# FE.net
KiCad netlist of a schematic drawn in Altium Designer
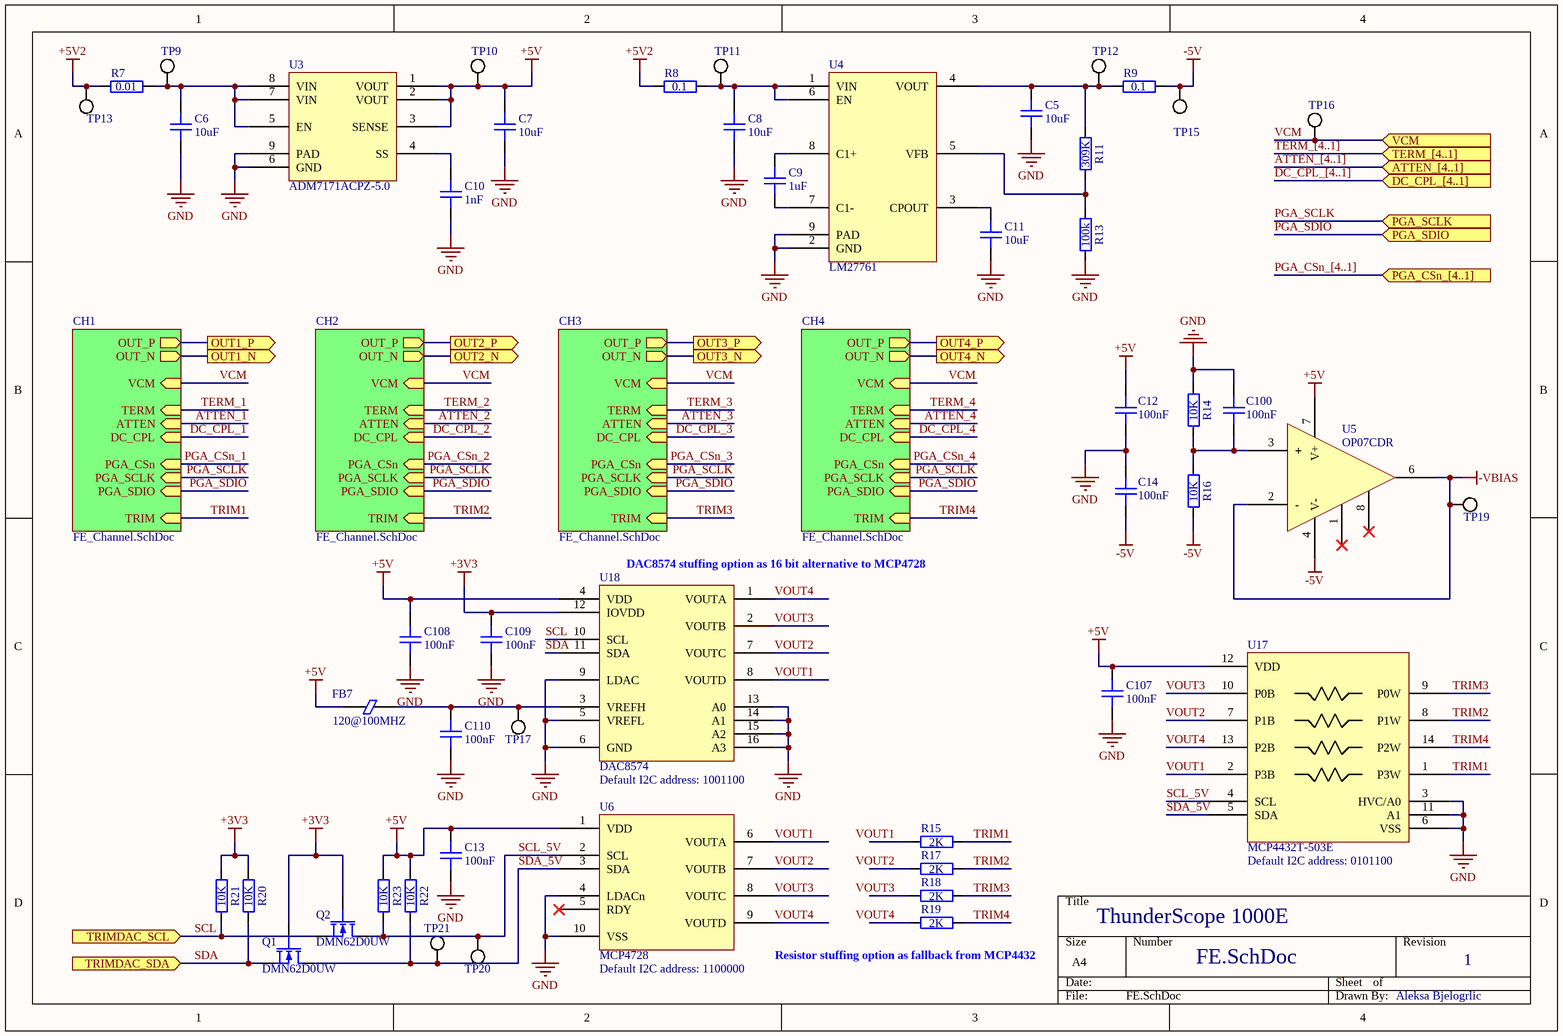
[diagram p0: FE.SchDoc]

(export (version "E")
  (design (tool "Eeschema 10.0.6"))
  (components
    (comp (ref "C5")
      (value "10uF")
      (footprint "GEN_C_0603")
      (libsource (lib "DSO") (part "CAP 10uF 10V X5R 0603"))
    )
    (comp (ref "C6")
      (value "10uF")
      (footprint "GEN_C_0603")
      (libsource (lib "DSO") (part "CAP 10uF 10V X5R 0603"))
    )
    (comp (ref "C7")
      (value "10uF")
      (footprint "GEN_C_0603")
      (libsource (lib "DSO") (part "CAP 10uF 10V X5R 0603"))
    )
    (comp (ref "C8")
      (value "10uF")
      (footprint "GEN_C_0603")
      (libsource (lib "DSO") (part "CAP 10uF 10V X5R 0603"))
    )
    (comp (ref "C9")
      (value "1uF")
      (footprint "GEN_C_0402")
      (libsource (lib "DSO") (part "CAP 1uF 25V X5R 0402"))
    )
    (comp (ref "C10")
      (value "1nF")
      (footprint "GEN_C_0402")
      (libsource (lib "DSO") (part "CAP 1nF 50V C0G 0402"))
    )
    (comp (ref "C11")
      (value "10uF")
      (footprint "GEN_C_0603")
      (libsource (lib "DSO") (part "CAP 10uF 10V X5R 0603"))
    )
    (comp (ref "C12")
      (value "100nF")
      (footprint "GEN_C_0402")
      (libsource (lib "DSO") (part "CAP 100nF 16V X7R 0402"))
    )
    (comp (ref "C13")
      (value "100nF")
      (footprint "GEN_C_0402")
      (libsource (lib "DSO") (part "CAP 100nF 16V X7R 0402"))
    )
    (comp (ref "C14")
      (value "100nF")
      (footprint "GEN_C_0402")
      (libsource (lib "DSO") (part "CAP 100nF 16V X7R 0402"))
    )
    (comp (ref "C100")
      (value "100nF")
      (footprint "GEN_C_0402")
      (libsource (lib "DSO") (part "CAP 100nF 16V X7R 0402"))
    )
    (comp (ref "C107")
      (value "100nF")
      (footprint "GEN_C_0402")
      (libsource (lib "DSO") (part "CAP 100nF 16V X7R 0402"))
    )
    (comp (ref "C108")
      (value "100nF")
      (footprint "GEN_C_0402")
      (libsource (lib "DSO") (part "CAP 100nF 16V X7R 0402"))
    )
    (comp (ref "C109")
      (value "100nF")
      (footprint "GEN_C_0402")
      (libsource (lib "DSO") (part "CAP 100nF 16V X7R 0402"))
    )
    (comp (ref "C110")
      (value "100nF")
      (footprint "GEN_C_0402")
      (libsource (lib "DSO") (part "CAP 100nF 16V X7R 0402"))
    )
    (comp (ref "FB7")
      (value "120@100MHZ")
      (footprint "GEN_R_0402")
      (libsource (lib "DSO") (part "FERRITE BEAD 120 OHM 0402"))
    )
    (comp (ref "Q1")
      (value "DMN62D0UW")
      (footprint "GEN_SOT_323")
      (libsource (lib "DSO") (part "NMOS DMN62D0UW"))
    )
    (comp (ref "Q2")
      (value "DMN62D0UW")
      (footprint "GEN_SOT_323")
      (libsource (lib "DSO") (part "NMOS DMN62D0UW"))
    )
    (comp (ref "R7")
      (value "0.01")
      (footprint "GEN_R_0603")
      (fields (field (name "TOLERANCE") "1%"))
      (libsource (lib "DSO") (part "RES 0.01 OHM 1% 1/4W 0603"))
    )
    (comp (ref "R8")
      (value "0.1")
      (footprint "GEN_R_0402")
      (fields (field (name "TOLERANCE") "1%"))
      (libsource (lib "DSO") (part "RES 0.1 OHM 1% 1/6W 0402"))
    )
    (comp (ref "R9")
      (value "0.1")
      (footprint "GEN_R_0402")
      (fields (field (name "TOLERANCE") "1%"))
      (libsource (lib "DSO") (part "RES 0.1 OHM 1% 1/6W 0402"))
    )
    (comp (ref "R11")
      (value "309K")
      (footprint "GEN_R_0402")
      (fields (field (name "TOLERANCE") "1%"))
      (libsource (lib "DSO") (part "RES 309K OHM 1% 1/16W 0402"))
    )
    (comp (ref "R13")
      (value "100k")
      (footprint "GEN_R_0402")
      (fields (field (name "TOLERANCE") "1%"))
      (libsource (lib "DSO") (part "RES 100K OHM 1% 1/10W 0402"))
    )
    (comp (ref "R14")
      (value "10K")
      (footprint "GEN_R_0402")
      (fields (field (name "TOLERANCE") "1%"))
      (libsource (lib "DSO") (part "RES 10K OHM 1% 1/10W 0402"))
    )
    (comp (ref "R15")
      (value "2K")
      (footprint "GEN_R_0402")
      (fields (field (name "TOLERANCE") "1%"))
      (libsource (lib "DSO") (part "RES 2K OHM 1% 1/16W 0402"))
    )
    (comp (ref "R16")
      (value "10K")
      (footprint "GEN_R_0402")
      (fields (field (name "TOLERANCE") "1%"))
      (libsource (lib "DSO") (part "RES 10K OHM 1% 1/10W 0402"))
    )
    (comp (ref "R17")
      (value "2K")
      (footprint "GEN_R_0402")
      (fields (field (name "TOLERANCE") "1%"))
      (libsource (lib "DSO") (part "RES 2K OHM 1% 1/16W 0402"))
    )
    (comp (ref "R18")
      (value "2K")
      (footprint "GEN_R_0402")
      (fields (field (name "TOLERANCE") "1%"))
      (libsource (lib "DSO") (part "RES 2K OHM 1% 1/16W 0402"))
    )
    (comp (ref "R19")
      (value "2K")
      (footprint "GEN_R_0402")
      (fields (field (name "TOLERANCE") "1%"))
      (libsource (lib "DSO") (part "RES 2K OHM 1% 1/16W 0402"))
    )
    (comp (ref "R20")
      (value "10K")
      (footprint "GEN_R_0402")
      (fields (field (name "TOLERANCE") "1%"))
      (libsource (lib "DSO") (part "RES 10K OHM 1% 1/10W 0402"))
    )
    (comp (ref "R21")
      (value "10K")
      (footprint "GEN_R_0402")
      (fields (field (name "TOLERANCE") "1%"))
      (libsource (lib "DSO") (part "RES 10K OHM 1% 1/10W 0402"))
    )
    (comp (ref "R22")
      (value "10K")
      (footprint "GEN_R_0402")
      (fields (field (name "TOLERANCE") "1%"))
      (libsource (lib "DSO") (part "RES 10K OHM 1% 1/10W 0402"))
    )
    (comp (ref "R23")
      (value "10K")
      (footprint "GEN_R_0402")
      (fields (field (name "TOLERANCE") "1%"))
      (libsource (lib "DSO") (part "RES 10K OHM 1% 1/10W 0402"))
    )
    (comp (ref "TP9") (value "PCB") (footprint "GEN_TP_PCB") (libsource (lib "DSO") (part "TP PCB 1mm")))
    (comp (ref "TP10") (value "PCB") (footprint "GEN_TP_PCB") (libsource (lib "DSO") (part "TP PCB 1mm")))
    (comp (ref "TP11") (value "PCB") (footprint "GEN_TP_PCB") (libsource (lib "DSO") (part "TP PCB 1mm")))
    (comp (ref "TP12") (value "PCB") (footprint "GEN_TP_PCB") (libsource (lib "DSO") (part "TP PCB 1mm")))
    (comp (ref "TP13") (value "PCB") (footprint "GEN_TP_PCB") (libsource (lib "DSO") (part "TP PCB 1mm")))
    (comp (ref "TP15") (value "PCB") (footprint "GEN_TP_PCB") (libsource (lib "DSO") (part "TP PCB 1mm")))
    (comp (ref "TP16") (value "PCB") (footprint "GEN_TP_PCB") (libsource (lib "DSO") (part "TP PCB 1mm")))
    (comp (ref "TP17") (value "PCB") (footprint "GEN_TP_PCB") (libsource (lib "DSO") (part "TP PCB 1mm")))
    (comp (ref "TP19") (value "PCB") (footprint "GEN_TP_PCB") (libsource (lib "DSO") (part "TP PCB 1mm")))
    (comp (ref "TP20") (value "PCB") (footprint "GEN_TP_PCB") (libsource (lib "DSO") (part "TP PCB 1mm")))
    (comp (ref "TP21") (value "PCB") (footprint "GEN_TP_PCB") (libsource (lib "DSO") (part "TP PCB 1mm")))
    (comp (ref "U3")
      (value "ADM7171ACPZ-5.0")
      (footprint "AD_DFN8_CP-8-21")
      (libsource (lib "DSO") (part "IC LDO ADM7171ACPZ-5.0"))
    )
    (comp (ref "U4")
      (value "LM27761")
      (footprint "TI_WSON8_DSG0008A")
      (libsource (lib "DSO") (part "IC CPUMP LM27761"))
    )
    (comp (ref "U5")
      (value "OP07CDR")
      (footprint "TI_SOIC8_D0008A")
      (libsource (lib "DSO") (part "IC OPAMP OP07CDR"))
    )
    (comp (ref "U6")
      (value "MCP4728")
      (footprint "MC_MSOP10_UN")
      (libsource (lib "DSO") (part "IC DAC QUAD MCP4728"))
    )
    (comp (ref "U17")
      (value "MCP4432T-503E")
      (footprint "MC_TSSOP14")
      (libsource (lib "DSO") (part "IC DIGIPOT QUAD MCP4432T-503E"))
    )
    (comp (ref "U18")
      (value "DAC8574")
      (footprint "TI_TSSOP16_PW0016A")
      (libsource (lib "DSO") (part "IC DAC QUAD DAC8574"))
    )
  )
  (nets
    (net (code "1") (name "+3V3") (class "Default")
      (node (ref "C109") (pin "2") (pinfunction "2_2") (pintype "passive"))
      (node (ref "Q1") (pin "2") (pinfunction "G_2") (pintype "passive"))
      (node (ref "Q2") (pin "2") (pinfunction "G_2") (pintype "passive"))
      (node (ref "R20") (pin "2") (pinfunction "2_2") (pintype "passive"))
      (node (ref "R21") (pin "2") (pinfunction "2_2") (pintype "passive"))
      (node (ref "U18") (pin "12") (pinfunction "IOVDD_12") (pintype "power_in"))
    )
    (net (code "2") (name "+5V") (class "Default")
      (node (ref "C107") (pin "2") (pinfunction "2_2") (pintype "passive"))
      (node (ref "C108") (pin "2") (pinfunction "2_2") (pintype "passive"))
      (node (ref "C12") (pin "1") (pinfunction "1_1") (pintype "passive"))
      (node (ref "C13") (pin "2") (pinfunction "2_2") (pintype "passive"))
      (node (ref "C7") (pin "2") (pinfunction "2_2") (pintype "passive"))
      (node (ref "FB7") (pin "2") (pinfunction "2_2") (pintype "passive"))
      (node (ref "R22") (pin "2") (pinfunction "2_2") (pintype "passive"))
      (node (ref "R23") (pin "2") (pinfunction "2_2") (pintype "passive"))
      (node (ref "TP10") (pin "1") (pinfunction "1_1") (pintype "passive"))
      (node (ref "U17") (pin "12") (pinfunction "VDD_12") (pintype "power_in"))
      (node (ref "U18") (pin "4") (pinfunction "VDD_4") (pintype "power_in"))
      (node (ref "U3") (pin "1") (pinfunction "VOUT_1") (pintype "power_in"))
      (node (ref "U3") (pin "2") (pinfunction "VOUT_2") (pintype "power_in"))
      (node (ref "U3") (pin "3") (pinfunction "SENSE_3") (pintype "passive"))
      (node (ref "U5") (pin "7") (pinfunction "V+_7") (pintype "passive"))
      (node (ref "U6") (pin "1") (pinfunction "VDD_1") (pintype "power_in"))
    )
    (net (code "3") (name "+5V2") (class "Default")
      (node (ref "R7") (pin "1") (pinfunction "1_1") (pintype "passive"))
      (node (ref "R8") (pin "1") (pinfunction "1_1") (pintype "passive"))
      (node (ref "TP13") (pin "1") (pinfunction "1_1") (pintype "passive"))
    )
    (net (code "4") (name "-5V") (class "Default")
      (node (ref "C14") (pin "2") (pinfunction "2_2") (pintype "passive"))
      (node (ref "R16") (pin "1") (pinfunction "1_1") (pintype "passive"))
      (node (ref "R9") (pin "2") (pinfunction "2_2") (pintype "passive"))
      (node (ref "TP15") (pin "1") (pinfunction "1_1") (pintype "passive"))
      (node (ref "U5") (pin "4") (pinfunction "V-_4") (pintype "passive"))
    )
    (net (code "5") (name "-VBIAS") (class "Default")
      (node (ref "TP19") (pin "1") (pinfunction "1_1") (pintype "passive"))
      (node (ref "U5") (pin "2") (pinfunction "-_2") (pintype "passive"))
      (node (ref "U5") (pin "6") (pinfunction "OUT_6") (pintype "passive"))
    )
    (net (code "31") (name "/SCL") (class "Default")
      (node (ref "Q2") (pin "3") (pinfunction "S_3") (pintype "passive"))
      (node (ref "R21") (pin "1") (pinfunction "1_1") (pintype "passive"))
      (node (ref "U18") (pin "10") (pinfunction "SCL_10") (pintype "passive"))
    )
    (net (code "32") (name "/SCL_5V") (class "Default")
      (node (ref "Q2") (pin "1") (pinfunction "D_1") (pintype "passive"))
      (node (ref "R23") (pin "1") (pinfunction "1_1") (pintype "passive"))
      (node (ref "TP20") (pin "1") (pinfunction "1_1") (pintype "passive"))
      (node (ref "U17") (pin "4") (pinfunction "SCL_4") (pintype "passive"))
      (node (ref "U6") (pin "2") (pinfunction "SCL_2") (pintype "passive"))
    )
    (net (code "33") (name "/SDA") (class "Default")
      (node (ref "Q1") (pin "3") (pinfunction "S_3") (pintype "passive"))
      (node (ref "R20") (pin "1") (pinfunction "1_1") (pintype "passive"))
      (node (ref "U18") (pin "11") (pinfunction "SDA_11") (pintype "passive"))
    )
    (net (code "34") (name "/SDA_5V") (class "Default")
      (node (ref "Q1") (pin "1") (pinfunction "D_1") (pintype "passive"))
      (node (ref "R22") (pin "1") (pinfunction "1_1") (pintype "passive"))
      (node (ref "TP21") (pin "1") (pinfunction "1_1") (pintype "passive"))
      (node (ref "U17") (pin "5") (pinfunction "SDA_5") (pintype "passive"))
      (node (ref "U6") (pin "3") (pinfunction "SDA_3") (pintype "passive"))
    )
    (net (code "40") (name "/TRIM1") (class "Default")
      (node (ref "R15") (pin "1") (pinfunction "1_1") (pintype "passive"))
      (node (ref "U17") (pin "1") (pinfunction "P3W_1") (pintype "passive"))
    )
    (net (code "41") (name "/TRIM2") (class "Default")
      (node (ref "R17") (pin "1") (pinfunction "1_1") (pintype "passive"))
      (node (ref "U17") (pin "8") (pinfunction "P1W_8") (pintype "passive"))
    )
    (net (code "42") (name "/TRIM3") (class "Default")
      (node (ref "R18") (pin "1") (pinfunction "1_1") (pintype "passive"))
      (node (ref "U17") (pin "9") (pinfunction "P0W_9") (pintype "passive"))
    )
    (net (code "43") (name "/TRIM4") (class "Default")
      (node (ref "R19") (pin "1") (pinfunction "1_1") (pintype "passive"))
      (node (ref "U17") (pin "14") (pinfunction "P2W_14") (pintype "passive"))
    )
    (net (code "44") (name "/VCM") (class "Default")
      (node (ref "TP16") (pin "1") (pinfunction "1_1") (pintype "passive"))
    )
    (net (code "45") (name "/VOUT1") (class "Default")
      (node (ref "R15") (pin "2") (pinfunction "2_2") (pintype "passive"))
      (node (ref "U17") (pin "2") (pinfunction "P3B_2") (pintype "passive"))
      (node (ref "U18") (pin "8") (pinfunction "VOUTD_8") (pintype "passive"))
      (node (ref "U6") (pin "6") (pinfunction "VOUTA_6") (pintype "passive"))
    )
    (net (code "46") (name "/VOUT2") (class "Default")
      (node (ref "R17") (pin "2") (pinfunction "2_2") (pintype "passive"))
      (node (ref "U17") (pin "7") (pinfunction "P1B_7") (pintype "passive"))
      (node (ref "U18") (pin "7") (pinfunction "VOUTC_7") (pintype "passive"))
      (node (ref "U6") (pin "7") (pinfunction "VOUTB_7") (pintype "passive"))
    )
    (net (code "47") (name "/VOUT3") (class "Default")
      (node (ref "R18") (pin "2") (pinfunction "2_2") (pintype "passive"))
      (node (ref "U17") (pin "10") (pinfunction "P0B_10") (pintype "passive"))
      (node (ref "U18") (pin "2") (pinfunction "VOUTB_2") (pintype "passive"))
      (node (ref "U6") (pin "8") (pinfunction "VOUTC_8") (pintype "passive"))
    )
    (net (code "48") (name "/VOUT4") (class "Default")
      (node (ref "R19") (pin "2") (pinfunction "2_2") (pintype "passive"))
      (node (ref "U17") (pin "13") (pinfunction "P2B_13") (pintype "passive"))
      (node (ref "U18") (pin "1") (pinfunction "VOUTA_1") (pintype "passive"))
      (node (ref "U6") (pin "9") (pinfunction "VOUTD_9") (pintype "passive"))
    )
    (net (code "49") (name "GND") (class "Default")
      (node (ref "C10") (pin "1") (pinfunction "1_1") (pintype "passive"))
      (node (ref "C100") (pin "1") (pinfunction "1_1") (pintype "passive"))
      (node (ref "C107") (pin "1") (pinfunction "1_1") (pintype "passive"))
      (node (ref "C108") (pin "1") (pinfunction "1_1") (pintype "passive"))
      (node (ref "C109") (pin "1") (pinfunction "1_1") (pintype "passive"))
      (node (ref "C11") (pin "1") (pinfunction "1_1") (pintype "passive"))
      (node (ref "C110") (pin "1") (pinfunction "1_1") (pintype "passive"))
      (node (ref "C12") (pin "2") (pinfunction "2_2") (pintype "passive"))
      (node (ref "C13") (pin "1") (pinfunction "1_1") (pintype "passive"))
      (node (ref "C14") (pin "1") (pinfunction "1_1") (pintype "passive"))
      (node (ref "C5") (pin "1") (pinfunction "1_1") (pintype "passive"))
      (node (ref "C6") (pin "1") (pinfunction "1_1") (pintype "passive"))
      (node (ref "C7") (pin "1") (pinfunction "1_1") (pintype "passive"))
      (node (ref "C8") (pin "1") (pinfunction "1_1") (pintype "passive"))
      (node (ref "R13") (pin "1") (pinfunction "1_1") (pintype "passive"))
      (node (ref "R14") (pin "2") (pinfunction "2_2") (pintype "passive"))
      (node (ref "U17") (pin "11") (pinfunction "A1_11") (pintype "passive"))
      (node (ref "U17") (pin "3") (pinfunction "HVC/A0_3") (pintype "passive"))
      (node (ref "U17") (pin "6") (pinfunction "VSS_6") (pintype "power_in"))
      (node (ref "U18") (pin "13") (pinfunction "A0_13") (pintype "passive"))
      (node (ref "U18") (pin "14") (pinfunction "A1_14") (pintype "passive"))
      (node (ref "U18") (pin "15") (pinfunction "A2_15") (pintype "passive"))
      (node (ref "U18") (pin "16") (pinfunction "A3_16") (pintype "passive"))
      (node (ref "U18") (pin "5") (pinfunction "VREFL_5") (pintype "passive"))
      (node (ref "U18") (pin "6") (pinfunction "GND_6") (pintype "power_in"))
      (node (ref "U18") (pin "9") (pinfunction "LDAC_9") (pintype "passive"))
      (node (ref "U3") (pin "6") (pinfunction "GND_6") (pintype "power_in"))
      (node (ref "U3") (pin "9") (pinfunction "PAD_9") (pintype "passive"))
      (node (ref "U4") (pin "2") (pinfunction "GND_2") (pintype "power_in"))
      (node (ref "U4") (pin "9") (pinfunction "PAD_9") (pintype "power_in"))
      (node (ref "U6") (pin "10") (pinfunction "VSS_10") (pintype "power_in"))
      (node (ref "U6") (pin "4") (pinfunction "LDACn_4") (pintype "passive"))
    )
    (net (code "50") (name "Net-(U3-EN)") (class "Default")
      (node (ref "C6") (pin "2") (pinfunction "2_2") (pintype "passive"))
      (node (ref "R7") (pin "2") (pinfunction "2_2") (pintype "passive"))
      (node (ref "TP9") (pin "1") (pinfunction "1_1") (pintype "passive"))
      (node (ref "U3") (pin "5") (pinfunction "EN_5") (pintype "passive"))
      (node (ref "U3") (pin "7") (pinfunction "VIN_7") (pintype "power_in"))
      (node (ref "U3") (pin "8") (pinfunction "VIN_8") (pintype "power_in"))
    )
    (net (code "51") (name "Net-(U3-SS)") (class "Default")
      (node (ref "C10") (pin "2") (pinfunction "2_2") (pintype "passive"))
      (node (ref "U3") (pin "4") (pinfunction "SS_4") (pintype "passive"))
    )
    (net (code "52") (name "Net-(U4-C1+)") (class "Default")
      (node (ref "C9") (pin "2") (pinfunction "2_2") (pintype "passive"))
      (node (ref "U4") (pin "8") (pinfunction "C1+_8") (pintype "passive"))
    )
    (net (code "53") (name "Net-(U4-C1-)") (class "Default")
      (node (ref "C9") (pin "1") (pinfunction "1_1") (pintype "passive"))
      (node (ref "U4") (pin "7") (pinfunction "C1-_7") (pintype "passive"))
    )
    (net (code "54") (name "Net-(U4-CPOUT)") (class "Default")
      (node (ref "C11") (pin "2") (pinfunction "2_2") (pintype "passive"))
      (node (ref "U4") (pin "3") (pinfunction "CPOUT_3") (pintype "passive"))
    )
    (net (code "55") (name "Net-(U4-EN)") (class "Default")
      (node (ref "C8") (pin "2") (pinfunction "2_2") (pintype "passive"))
      (node (ref "R8") (pin "2") (pinfunction "2_2") (pintype "passive"))
      (node (ref "TP11") (pin "1") (pinfunction "1_1") (pintype "passive"))
      (node (ref "U4") (pin "1") (pinfunction "VIN_1") (pintype "power_in"))
      (node (ref "U4") (pin "6") (pinfunction "EN_6") (pintype "passive"))
    )
    (net (code "56") (name "Net-(U4-VFB)") (class "Default")
      (node (ref "R11") (pin "1") (pinfunction "1_1") (pintype "passive"))
      (node (ref "R13") (pin "2") (pinfunction "2_2") (pintype "passive"))
      (node (ref "U4") (pin "5") (pinfunction "VFB_5") (pintype "passive"))
    )
    (net (code "57") (name "Net-(U4-VOUT)") (class "Default")
      (node (ref "C5") (pin "2") (pinfunction "2_2") (pintype "passive"))
      (node (ref "R11") (pin "2") (pinfunction "2_2") (pintype "passive"))
      (node (ref "R9") (pin "1") (pinfunction "1_1") (pintype "passive"))
      (node (ref "TP12") (pin "1") (pinfunction "1_1") (pintype "passive"))
      (node (ref "U4") (pin "4") (pinfunction "VOUT_4") (pintype "power_in"))
    )
    (net (code "58") (name "Net-(U5-+)") (class "Default")
      (node (ref "C100") (pin "2") (pinfunction "2_2") (pintype "passive"))
      (node (ref "R14") (pin "1") (pinfunction "1_1") (pintype "passive"))
      (node (ref "R16") (pin "2") (pinfunction "2_2") (pintype "passive"))
      (node (ref "U5") (pin "3") (pinfunction "+_3") (pintype "passive"))
    )
    (net (code "59") (name "Net-(U18-VREFH)") (class "Default")
      (node (ref "C110") (pin "2") (pinfunction "2_2") (pintype "passive"))
      (node (ref "FB7") (pin "1") (pinfunction "1_1") (pintype "passive"))
      (node (ref "TP17") (pin "1") (pinfunction "1_1") (pintype "passive"))
      (node (ref "U18") (pin "3") (pinfunction "VREFH_3") (pintype "passive"))
    )
    (net (code "60") (name "unconnected-(U5-N1-Pad1)") (class "Default")
      (node (ref "U5") (pin "1") (pinfunction "N1_1") (pintype "passive+no_connect"))
    )
    (net (code "61") (name "unconnected-(U5-N2-Pad8)") (class "Default")
      (node (ref "U5") (pin "8") (pinfunction "N2_8") (pintype "passive+no_connect"))
    )
    (net (code "62") (name "unconnected-(U6-RDY-Pad5)") (class "Default")
      (node (ref "U6") (pin "5") (pinfunction "RDY_5") (pintype "passive+no_connect"))
    )
  )
)
